# rpi_can.net
KiCad netlist of a schematic drawn in EAGLE
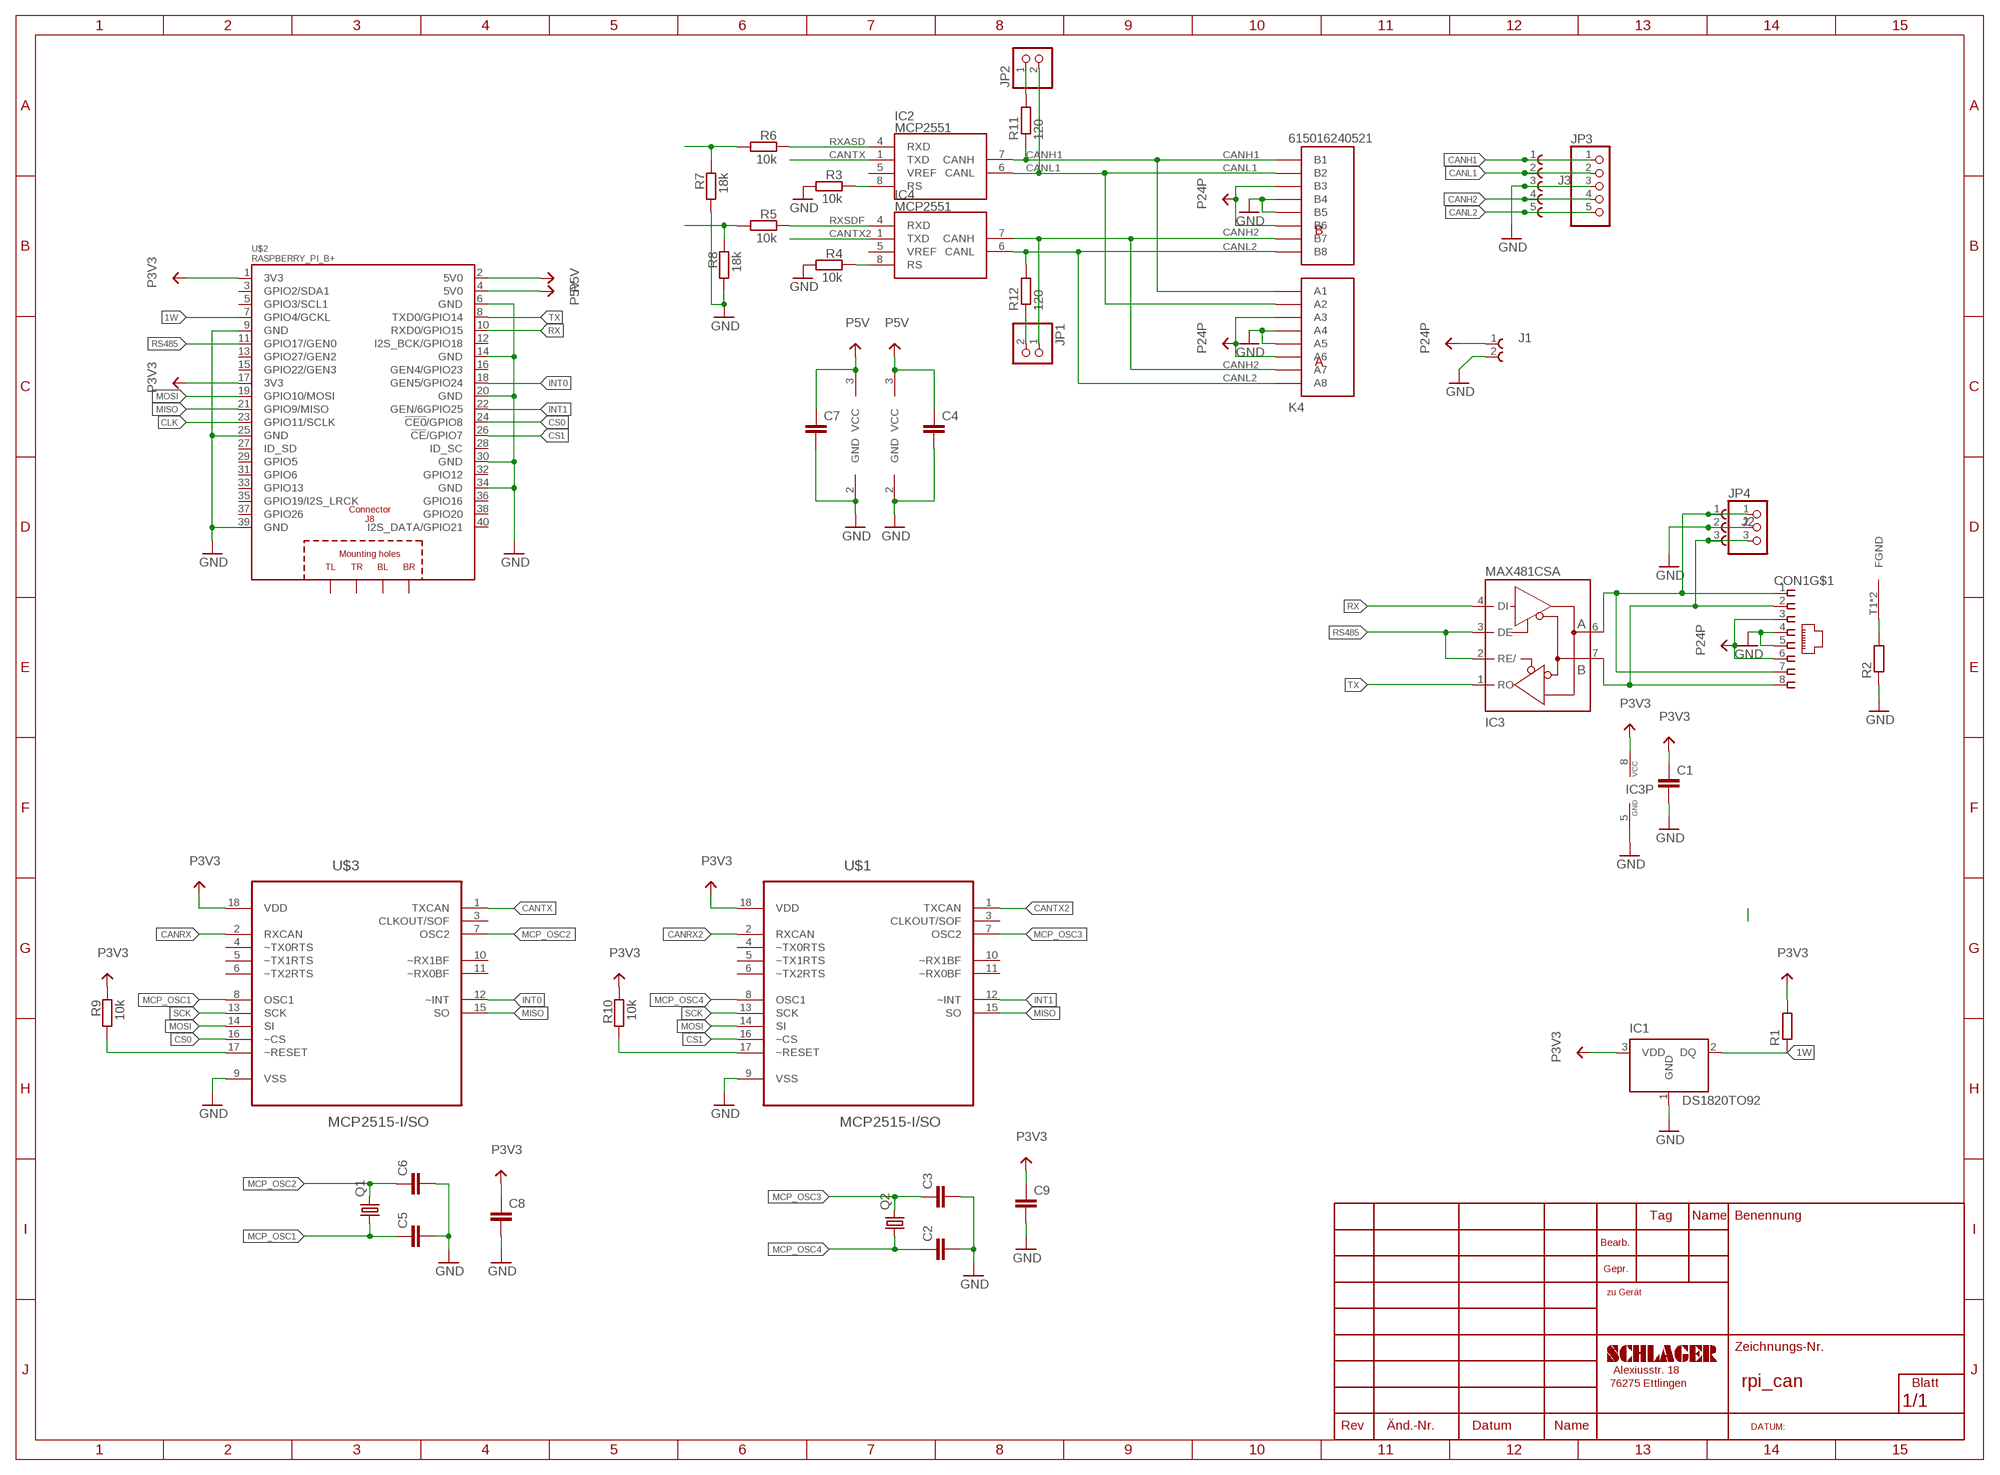
[diagram p0: schematic, sheet 1]

(export (version "E")
  (design (tool "Eeschema 10.0.6"))
  (components
    (comp (ref "C1")
      (value "C-EUC0805")
      (footprint "eagle-import:C0805")
      (libsource (lib "eagle-import") (part "C-EUC0805"))
    )
    (comp (ref "C2")
      (value "C-EUC0805")
      (footprint "eagle-import:C0805")
      (libsource (lib "eagle-import") (part "C-EUC0805"))
    )
    (comp (ref "C3")
      (value "C-EUC0805")
      (footprint "eagle-import:C0805")
      (libsource (lib "eagle-import") (part "C-EUC0805"))
    )
    (comp (ref "C4")
      (value "C-EUC0805")
      (footprint "eagle-import:C0805")
      (libsource (lib "eagle-import") (part "C-EUC0805"))
    )
    (comp (ref "C5")
      (value "C-EUC0805")
      (footprint "eagle-import:C0805")
      (libsource (lib "eagle-import") (part "C-EUC0805"))
    )
    (comp (ref "C6")
      (value "C-EUC0805")
      (footprint "eagle-import:C0805")
      (libsource (lib "eagle-import") (part "C-EUC0805"))
    )
    (comp (ref "C7")
      (value "C-EUC0805")
      (footprint "eagle-import:C0805")
      (libsource (lib "eagle-import") (part "C-EUC0805"))
    )
    (comp (ref "C8")
      (value "C-EUC0805")
      (footprint "eagle-import:C0805")
      (libsource (lib "eagle-import") (part "C-EUC0805"))
    )
    (comp (ref "C9")
      (value "C-EUC0805")
      (footprint "eagle-import:C0805")
      (libsource (lib "eagle-import") (part "C-EUC0805"))
    )
    (comp (ref "CON1")
      (value "MEBP_8-8G")
      (footprint "eagle-import:MEBP")
      (libsource (lib "eagle-import") (part "MEBP_8-8G"))
    )
    (comp (ref "IC1")
      (value "DS1820TO92")
      (footprint "eagle-import:TO-92")
      (libsource (lib "eagle-import") (part "DS1820TO92"))
    )
    (comp (ref "IC2")
      (value "MCP2551")
      (footprint "eagle-import:SO-8")
      (libsource (lib "eagle-import") (part "MCP2551"))
    )
    (comp (ref "IC3")
      (value "MAX481CSA")
      (footprint "eagle-import:SO08")
      (fields (field (name "MF") "MAXIM"))
      (libsource (lib "eagle-import") (part "MAX481CSA"))
    )
    (comp (ref "IC4")
      (value "MCP2551")
      (footprint "eagle-import:SO-8")
      (libsource (lib "eagle-import") (part "MCP2551"))
    )
    (comp (ref "J1")
      (value "691322310002")
      (footprint "eagle-import:691322310002")
      (libsource (lib "eagle-import") (part "691322310002"))
    )
    (comp (ref "J2")
      (value "691322310003")
      (footprint "eagle-import:691322310003")
      (libsource (lib "eagle-import") (part "691322310003"))
    )
    (comp (ref "J3")
      (value "691322310005")
      (footprint "eagle-import:691322310005")
      (libsource (lib "eagle-import") (part "691322310005"))
    )
    (comp (ref "JP1")
      (value "PINHD-1X2")
      (footprint "eagle-import:1X02")
      (libsource (lib "eagle-import") (part "PINHD-1X2"))
    )
    (comp (ref "JP2")
      (value "PINHD-1X2")
      (footprint "eagle-import:1X02")
      (libsource (lib "eagle-import") (part "PINHD-1X2"))
    )
    (comp (ref "JP3")
      (value "PINHD-1X5")
      (footprint "eagle-import:1X05")
      (libsource (lib "eagle-import") (part "PINHD-1X5"))
    )
    (comp (ref "JP4")
      (value "PINHD-1X3")
      (footprint "eagle-import:1X03")
      (libsource (lib "eagle-import") (part "PINHD-1X3"))
    )
    (comp (ref "K4")
      (value "615016240521")
      (footprint "eagle-import:615016240521")
      (libsource (lib "eagle-import") (part "615016240521"))
    )
    (comp (ref "Q1")
      (value "CRYSTALHC49S")
      (footprint "eagle-import:HC49_S")
      (libsource (lib "eagle-import") (part "CRYSTALHC49S"))
    )
    (comp (ref "Q2")
      (value "CRYSTALHC49S")
      (footprint "eagle-import:HC49_S")
      (libsource (lib "eagle-import") (part "CRYSTALHC49S"))
    )
    (comp (ref "R1")
      (value "R-EU_R0805")
      (footprint "eagle-import:R0805")
      (libsource (lib "eagle-import") (part "R-EU_R0805"))
    )
    (comp (ref "R2")
      (value "R-EU_R0805")
      (footprint "eagle-import:R0805")
      (libsource (lib "eagle-import") (part "R-EU_R0805"))
    )
    (comp (ref "R3")
      (value "10k")
      (footprint "eagle-import:R0805")
      (libsource (lib "eagle-import") (part "R-EU_R0805"))
    )
    (comp (ref "R4")
      (value "10k")
      (footprint "eagle-import:R0805")
      (libsource (lib "eagle-import") (part "R-EU_R0805"))
    )
    (comp (ref "R5")
      (value "10k")
      (footprint "eagle-import:R0805")
      (libsource (lib "eagle-import") (part "R-EU_R0805"))
    )
    (comp (ref "R6")
      (value "10k")
      (footprint "eagle-import:R0805")
      (libsource (lib "eagle-import") (part "R-EU_R0805"))
    )
    (comp (ref "R7")
      (value "18k")
      (footprint "eagle-import:R0805")
      (libsource (lib "eagle-import") (part "R-EU_R0805"))
    )
    (comp (ref "R8")
      (value "18k")
      (footprint "eagle-import:R0805")
      (libsource (lib "eagle-import") (part "R-EU_R0805"))
    )
    (comp (ref "R9")
      (value "10k")
      (footprint "eagle-import:R0805")
      (libsource (lib "eagle-import") (part "R-EU_R0805"))
    )
    (comp (ref "R10")
      (value "10k")
      (footprint "eagle-import:R0805")
      (libsource (lib "eagle-import") (part "R-EU_R0805"))
    )
    (comp (ref "R11")
      (value "120")
      (footprint "eagle-import:R0805")
      (libsource (lib "eagle-import") (part "R-EU_R0805"))
    )
    (comp (ref "R12")
      (value "120")
      (footprint "eagle-import:R0805")
      (libsource (lib "eagle-import") (part "R-EU_R0805"))
    )
    (comp (ref "U$1")
      (value "MCP2515-I/SO")
      (footprint "eagle-import:SOIC127P1034X264-18N")
      (libsource (lib "eagle-import") (part "MCP2515-I/SO"))
    )
    (comp (ref "U$2")
      (value "RASPBERRY_PI_B+")
      (footprint "eagle-import:RASPBERRY_PI_B+")
      (libsource (lib "eagle-import") (part "RASPBERRY_PI_B+"))
    )
    (comp (ref "U$3")
      (value "MCP2515-I/SO")
      (footprint "eagle-import:SOIC127P1034X264-18N")
      (libsource (lib "eagle-import") (part "MCP2515-I/SO"))
    )
  )
  (nets
    (net (code "1") (name "/RXASD") (class "Default")
      (node (ref "IC2") (pin "4") (pinfunction "RXD_4") (pintype "bidirectional"))
      (node (ref "R6") (pin "1") (pinfunction "1_1") (pintype "passive"))
    )
    (net (code "2") (name "/RXSDF") (class "Default")
      (node (ref "IC4") (pin "4") (pinfunction "RXD_4") (pintype "bidirectional"))
      (node (ref "R5") (pin "1") (pinfunction "1_1") (pintype "passive"))
    )
    (net (code "3") (name "1W") (class "Default")
      (node (ref "IC1") (pin "2") (pinfunction "DQ_2") (pintype "output"))
      (node (ref "R1") (pin "1") (pinfunction "1_1") (pintype "passive"))
      (node (ref "U$2") (pin "7") (pinfunction "GPIO4/GCKL_7") (pintype "bidirectional"))
    )
    (net (code "4") (name "CANH1") (class "Default")
      (node (ref "IC2") (pin "7") (pinfunction "CANH_7") (pintype "bidirectional"))
      (node (ref "J3") (pin "1") (pinfunction "1_1") (pintype "passive"))
      (node (ref "JP3") (pin "1") (pinfunction "1_1") (pintype "passive"))
      (node (ref "K4") (pin "A1") (pinfunction "A1_A1") (pintype "passive"))
      (node (ref "K4") (pin "B1") (pinfunction "B1_B1") (pintype "passive"))
      (node (ref "R11") (pin "1") (pinfunction "1_1") (pintype "passive"))
    )
    (net (code "5") (name "CANH2") (class "Default")
      (node (ref "IC4") (pin "7") (pinfunction "CANH_7") (pintype "bidirectional"))
      (node (ref "J3") (pin "4") (pinfunction "4_4") (pintype "passive"))
      (node (ref "JP1") (pin "1") (pinfunction "1_1") (pintype "passive"))
      (node (ref "JP3") (pin "4") (pinfunction "4_4") (pintype "passive"))
      (node (ref "K4") (pin "A7") (pinfunction "A7_A7") (pintype "passive"))
      (node (ref "K4") (pin "B7") (pinfunction "B7_B7") (pintype "passive"))
    )
    (net (code "6") (name "CANL1") (class "Default")
      (node (ref "IC2") (pin "6") (pinfunction "CANL_6") (pintype "bidirectional"))
      (node (ref "J3") (pin "2") (pinfunction "2_2") (pintype "passive"))
      (node (ref "JP2") (pin "2") (pinfunction "2_2") (pintype "passive"))
      (node (ref "JP3") (pin "2") (pinfunction "2_2") (pintype "passive"))
      (node (ref "K4") (pin "A2") (pinfunction "A2_A2") (pintype "passive"))
      (node (ref "K4") (pin "B2") (pinfunction "B2_B2") (pintype "passive"))
    )
    (net (code "7") (name "CANL2") (class "Default")
      (node (ref "IC4") (pin "6") (pinfunction "CANL_6") (pintype "bidirectional"))
      (node (ref "J3") (pin "5") (pinfunction "5_5") (pintype "passive"))
      (node (ref "JP3") (pin "5") (pinfunction "5_5") (pintype "passive"))
      (node (ref "K4") (pin "A8") (pinfunction "A8_A8") (pintype "passive"))
      (node (ref "K4") (pin "B8") (pinfunction "B8_B8") (pintype "passive"))
      (node (ref "R12") (pin "2") (pinfunction "2_2") (pintype "passive"))
    )
    (net (code "8") (name "CANRX") (class "Default")
      (node (ref "R6") (pin "2") (pinfunction "2_2") (pintype "passive"))
      (node (ref "R7") (pin "1") (pinfunction "1_1") (pintype "passive"))
      (node (ref "U$3") (pin "2") (pinfunction "RXCAN_2") (pintype "input"))
    )
    (net (code "9") (name "CANRX2") (class "Default")
      (node (ref "R5") (pin "2") (pinfunction "2_2") (pintype "passive"))
      (node (ref "R8") (pin "1") (pinfunction "1_1") (pintype "passive"))
      (node (ref "U$1") (pin "2") (pinfunction "RXCAN_2") (pintype "input"))
    )
    (net (code "10") (name "CANTX") (class "Default")
      (node (ref "IC2") (pin "1") (pinfunction "TXD_1") (pintype "bidirectional"))
      (node (ref "U$3") (pin "1") (pinfunction "TXCAN_1") (pintype "output"))
    )
    (net (code "11") (name "CANTX2") (class "Default")
      (node (ref "IC4") (pin "1") (pinfunction "TXD_1") (pintype "bidirectional"))
      (node (ref "U$1") (pin "1") (pinfunction "TXCAN_1") (pintype "output"))
    )
    (net (code "12") (name "CLK") (class "Default")
      (node (ref "U$2") (pin "23") (pinfunction "GPIO11/SCLK_23") (pintype "bidirectional"))
    )
    (net (code "13") (name "CS0") (class "Default")
      (node (ref "U$2") (pin "24") (pinfunction "~{CE0}/GPIO8_24") (pintype "bidirectional"))
      (node (ref "U$3") (pin "16") (pinfunction "~{CS}_16") (pintype "input"))
    )
    (net (code "14") (name "CS1") (class "Default")
      (node (ref "U$1") (pin "16") (pinfunction "~{CS}_16") (pintype "input"))
      (node (ref "U$2") (pin "26") (pinfunction "~{CE}/GPIO7_26") (pintype "bidirectional"))
    )
    (net (code "15") (name "GND") (class "Default")
      (node (ref "C1") (pin "2") (pinfunction "2_2") (pintype "passive"))
      (node (ref "C2") (pin "2") (pinfunction "2_2") (pintype "passive"))
      (node (ref "C3") (pin "2") (pinfunction "2_2") (pintype "passive"))
      (node (ref "C4") (pin "2") (pinfunction "2_2") (pintype "passive"))
      (node (ref "C5") (pin "2") (pinfunction "2_2") (pintype "passive"))
      (node (ref "C6") (pin "2") (pinfunction "2_2") (pintype "passive"))
      (node (ref "C7") (pin "2") (pinfunction "2_2") (pintype "passive"))
      (node (ref "C8") (pin "2") (pinfunction "2_2") (pintype "passive"))
      (node (ref "C9") (pin "2") (pinfunction "2_2") (pintype "passive"))
      (node (ref "CON1") (pin "4") (pinfunction "4_4") (pintype "passive"))
      (node (ref "CON1") (pin "5") (pinfunction "5_5") (pintype "passive"))
      (node (ref "IC1") (pin "1") (pinfunction "GND_1") (pintype "power_in"))
      (node (ref "IC2") (pin "2") (pinfunction "GND_2") (pintype "power_in"))
      (node (ref "IC3") (pin "5") (pinfunction "GND_5") (pintype "power_in"))
      (node (ref "IC4") (pin "2") (pinfunction "GND_2") (pintype "power_in"))
      (node (ref "J1") (pin "2") (pinfunction "2_2") (pintype "passive"))
      (node (ref "J2") (pin "2") (pinfunction "2_2") (pintype "passive"))
      (node (ref "J3") (pin "3") (pinfunction "3_3") (pintype "passive"))
      (node (ref "JP3") (pin "3") (pinfunction "3_3") (pintype "passive"))
      (node (ref "JP4") (pin "2") (pinfunction "2_2") (pintype "passive"))
      (node (ref "K4") (pin "A4") (pinfunction "A4_A4") (pintype "passive"))
      (node (ref "K4") (pin "A5") (pinfunction "A5_A5") (pintype "passive"))
      (node (ref "K4") (pin "B4") (pinfunction "B4_B4") (pintype "passive"))
      (node (ref "K4") (pin "B5") (pinfunction "B5_B5") (pintype "passive"))
      (node (ref "R2") (pin "1") (pinfunction "1_1") (pintype "passive"))
      (node (ref "R3") (pin "2") (pinfunction "2_2") (pintype "passive"))
      (node (ref "R4") (pin "2") (pinfunction "2_2") (pintype "passive"))
      (node (ref "R7") (pin "2") (pinfunction "2_2") (pintype "passive"))
      (node (ref "R8") (pin "2") (pinfunction "2_2") (pintype "passive"))
      (node (ref "U$1") (pin "9") (pinfunction "VSS_9") (pintype "power_in"))
      (node (ref "U$2") (pin "14") (pinfunction "GND_14") (pintype "power_in"))
      (node (ref "U$2") (pin "20") (pinfunction "GND_20") (pintype "power_in"))
      (node (ref "U$2") (pin "25") (pinfunction "GND_25") (pintype "power_in"))
      (node (ref "U$2") (pin "30") (pinfunction "GND_30") (pintype "power_in"))
      (node (ref "U$2") (pin "34") (pinfunction "GND_34") (pintype "power_in"))
      (node (ref "U$2") (pin "39") (pinfunction "GND_39") (pintype "power_in"))
      (node (ref "U$2") (pin "6") (pinfunction "GND_6") (pintype "power_in"))
      (node (ref "U$2") (pin "9") (pinfunction "GND_9") (pintype "power_in"))
      (node (ref "U$3") (pin "9") (pinfunction "VSS_9") (pintype "power_in"))
    )
    (net (code "16") (name "INT0") (class "Default")
      (node (ref "U$2") (pin "18") (pinfunction "GEN5/GPIO24_18") (pintype "bidirectional"))
      (node (ref "U$3") (pin "12") (pinfunction "~{INT}_12") (pintype "output"))
    )
    (net (code "17") (name "INT1") (class "Default")
      (node (ref "U$1") (pin "12") (pinfunction "~{INT}_12") (pintype "output"))
      (node (ref "U$2") (pin "22") (pinfunction "GEN/6GPIO25_22") (pintype "bidirectional"))
    )
    (net (code "18") (name "MCP_OSC1") (class "Default")
      (node (ref "C5") (pin "1") (pinfunction "1_1") (pintype "passive"))
      (node (ref "Q1") (pin "1") (pinfunction "1_1") (pintype "passive"))
      (node (ref "U$3") (pin "8") (pinfunction "OSC1_8") (pintype "input"))
    )
    (net (code "19") (name "MCP_OSC2") (class "Default")
      (node (ref "C6") (pin "1") (pinfunction "1_1") (pintype "passive"))
      (node (ref "Q1") (pin "2") (pinfunction "2_2") (pintype "passive"))
      (node (ref "U$3") (pin "7") (pinfunction "OSC2_7") (pintype "output"))
    )
    (net (code "20") (name "MCP_OSC3") (class "Default")
      (node (ref "C3") (pin "1") (pinfunction "1_1") (pintype "passive"))
      (node (ref "Q2") (pin "2") (pinfunction "2_2") (pintype "passive"))
      (node (ref "U$1") (pin "7") (pinfunction "OSC2_7") (pintype "output"))
    )
    (net (code "21") (name "MCP_OSC4") (class "Default")
      (node (ref "C2") (pin "1") (pinfunction "1_1") (pintype "passive"))
      (node (ref "Q2") (pin "1") (pinfunction "1_1") (pintype "passive"))
      (node (ref "U$1") (pin "8") (pinfunction "OSC1_8") (pintype "input"))
    )
    (net (code "22") (name "MISO") (class "Default")
      (node (ref "U$1") (pin "15") (pinfunction "SO_15") (pintype "output"))
      (node (ref "U$2") (pin "21") (pinfunction "GPIO9/MISO_21") (pintype "bidirectional"))
      (node (ref "U$3") (pin "15") (pinfunction "SO_15") (pintype "output"))
    )
    (net (code "23") (name "MOSI") (class "Default")
      (node (ref "U$1") (pin "14") (pinfunction "SI_14") (pintype "input"))
      (node (ref "U$2") (pin "19") (pinfunction "GPIO10/MOSI_19") (pintype "bidirectional"))
      (node (ref "U$3") (pin "14") (pinfunction "SI_14") (pintype "input"))
    )
    (net (code "24") (name "Net-(CON1B-FGND-PadT1)") (class "Default")
      (node (ref "CON1") (pin "T1") (pinfunction "FGND_T1") (pintype "power_in"))
      (node (ref "CON1") (pin "T2") (pinfunction "FGND_T2") (pintype "power_in"))
      (node (ref "R2") (pin "2") (pinfunction "2_2") (pintype "passive"))
    )
    (net (code "25") (name "Net-(IC2A-RS)") (class "Default")
      (node (ref "IC2") (pin "8") (pinfunction "RS_8") (pintype "bidirectional"))
      (node (ref "R3") (pin "1") (pinfunction "1_1") (pintype "passive"))
    )
    (net (code "26") (name "Net-(IC3A-A)") (class "Default")
      (node (ref "CON1") (pin "1") (pinfunction "1_1") (pintype "passive"))
      (node (ref "CON1") (pin "7") (pinfunction "7_7") (pintype "passive"))
      (node (ref "IC3") (pin "6") (pinfunction "A_6") (pintype "passive"))
      (node (ref "J2") (pin "1") (pinfunction "1_1") (pintype "passive"))
      (node (ref "JP4") (pin "1") (pinfunction "1_1") (pintype "passive"))
    )
    (net (code "27") (name "Net-(IC3A-B)") (class "Default")
      (node (ref "CON1") (pin "2") (pinfunction "2_2") (pintype "passive"))
      (node (ref "CON1") (pin "8") (pinfunction "8_8") (pintype "passive"))
      (node (ref "IC3") (pin "7") (pinfunction "B_7") (pintype "passive"))
      (node (ref "J2") (pin "3") (pinfunction "3_3") (pintype "passive"))
      (node (ref "JP4") (pin "3") (pinfunction "3_3") (pintype "passive"))
    )
    (net (code "28") (name "Net-(IC4A-RS)") (class "Default")
      (node (ref "IC4") (pin "8") (pinfunction "RS_8") (pintype "bidirectional"))
      (node (ref "R4") (pin "1") (pinfunction "1_1") (pintype "passive"))
    )
    (net (code "29") (name "Net-(JP1-Pad2)") (class "Default")
      (node (ref "JP1") (pin "2") (pinfunction "2_2") (pintype "passive"))
      (node (ref "R12") (pin "1") (pinfunction "1_1") (pintype "passive"))
    )
    (net (code "30") (name "Net-(JP2-Pad1)") (class "Default")
      (node (ref "JP2") (pin "1") (pinfunction "1_1") (pintype "passive"))
      (node (ref "R11") (pin "2") (pinfunction "2_2") (pintype "passive"))
    )
    (net (code "31") (name "Net-(U$1-~{RESET})") (class "Default")
      (node (ref "R10") (pin "2") (pinfunction "2_2") (pintype "passive"))
      (node (ref "U$1") (pin "17") (pinfunction "~{RESET}_17") (pintype "input"))
    )
    (net (code "32") (name "Net-(U$3-~{RESET})") (class "Default")
      (node (ref "R9") (pin "2") (pinfunction "2_2") (pintype "passive"))
      (node (ref "U$3") (pin "17") (pinfunction "~{RESET}_17") (pintype "input"))
    )
    (net (code "33") (name "P3V3") (class "Default")
      (node (ref "C1") (pin "1") (pinfunction "1_1") (pintype "passive"))
      (node (ref "C8") (pin "1") (pinfunction "1_1") (pintype "passive"))
      (node (ref "C9") (pin "1") (pinfunction "1_1") (pintype "passive"))
      (node (ref "IC1") (pin "3") (pinfunction "VDD_3") (pintype "input"))
      (node (ref "IC3") (pin "8") (pinfunction "VCC_8") (pintype "power_in"))
      (node (ref "R1") (pin "2") (pinfunction "2_2") (pintype "passive"))
      (node (ref "R10") (pin "1") (pinfunction "1_1") (pintype "passive"))
      (node (ref "R9") (pin "1") (pinfunction "1_1") (pintype "passive"))
      (node (ref "U$1") (pin "18") (pinfunction "VDD_18") (pintype "power_in"))
      (node (ref "U$2") (pin "1") (pinfunction "3V3_1") (pintype "power_in"))
      (node (ref "U$2") (pin "17") (pinfunction "3V3_17") (pintype "power_in"))
      (node (ref "U$3") (pin "18") (pinfunction "VDD_18") (pintype "power_in"))
    )
    (net (code "34") (name "P5V") (class "Default")
      (node (ref "C4") (pin "1") (pinfunction "1_1") (pintype "passive"))
      (node (ref "C7") (pin "1") (pinfunction "1_1") (pintype "passive"))
      (node (ref "IC2") (pin "3") (pinfunction "VCC_3") (pintype "power_in"))
      (node (ref "IC4") (pin "3") (pinfunction "VCC_3") (pintype "power_in"))
      (node (ref "U$2") (pin "2") (pinfunction "5V0_2") (pintype "power_in"))
      (node (ref "U$2") (pin "4") (pinfunction "5V0_4") (pintype "power_in"))
    )
    (net (code "35") (name "P24P") (class "Default")
      (node (ref "CON1") (pin "3") (pinfunction "3_3") (pintype "passive"))
      (node (ref "CON1") (pin "6") (pinfunction "6_6") (pintype "passive"))
      (node (ref "J1") (pin "1") (pinfunction "1_1") (pintype "passive"))
      (node (ref "K4") (pin "A3") (pinfunction "A3_A3") (pintype "passive"))
      (node (ref "K4") (pin "A6") (pinfunction "A6_A6") (pintype "passive"))
      (node (ref "K4") (pin "B3") (pinfunction "B3_B3") (pintype "passive"))
      (node (ref "K4") (pin "B6") (pinfunction "B6_B6") (pintype "passive"))
    )
    (net (code "36") (name "RS485") (class "Default")
      (node (ref "IC3") (pin "2") (pinfunction "RE/_2") (pintype "input"))
      (node (ref "IC3") (pin "3") (pinfunction "DE_3") (pintype "input"))
      (node (ref "U$2") (pin "11") (pinfunction "GPIO17/GEN0_11") (pintype "bidirectional"))
    )
    (net (code "37") (name "RX") (class "Default")
      (node (ref "IC3") (pin "4") (pinfunction "DI_4") (pintype "input"))
      (node (ref "U$2") (pin "10") (pinfunction "RXD0/GPIO15_10") (pintype "bidirectional"))
    )
    (net (code "38") (name "SCK") (class "Default")
      (node (ref "U$1") (pin "13") (pinfunction "SCK_13") (pintype "input"))
      (node (ref "U$3") (pin "13") (pinfunction "SCK_13") (pintype "input"))
    )
    (net (code "39") (name "TX") (class "Default")
      (node (ref "IC3") (pin "1") (pinfunction "RO_1") (pintype "output"))
      (node (ref "U$2") (pin "8") (pinfunction "TXD0/GPIO14_8") (pintype "bidirectional"))
    )
    (net (code "40") (name "unconnected-(IC2A-VREF-Pad5)") (class "Default")
      (node (ref "IC2") (pin "5") (pinfunction "VREF_5") (pintype "bidirectional"))
    )
    (net (code "41") (name "unconnected-(IC4A-VREF-Pad5)") (class "Default")
      (node (ref "IC4") (pin "5") (pinfunction "VREF_5") (pintype "bidirectional"))
    )
    (net (code "42") (name "unconnected-(U$1-CLKOUT{slash}SOF-Pad3)") (class "Default")
      (node (ref "U$1") (pin "3") (pinfunction "CLKOUT/SOF_3") (pintype "output"))
    )
    (net (code "43") (name "unconnected-(U$1-~{RX0BF}-Pad11)") (class "Default")
      (node (ref "U$1") (pin "11") (pinfunction "~{RX0BF}_11") (pintype "output"))
    )
    (net (code "44") (name "unconnected-(U$1-~{RX1BF}-Pad10)") (class "Default")
      (node (ref "U$1") (pin "10") (pinfunction "~{RX1BF}_10") (pintype "output"))
    )
    (net (code "45") (name "unconnected-(U$1-~{TX0RTS}-Pad4)") (class "Default")
      (node (ref "U$1") (pin "4") (pinfunction "~{TX0RTS}_4") (pintype "input"))
    )
    (net (code "46") (name "unconnected-(U$1-~{TX1RTS}-Pad5)") (class "Default")
      (node (ref "U$1") (pin "5") (pinfunction "~{TX1RTS}_5") (pintype "input"))
    )
    (net (code "47") (name "unconnected-(U$1-~{TX2RTS}-Pad6)") (class "Default")
      (node (ref "U$1") (pin "6") (pinfunction "~{TX2RTS}_6") (pintype "input"))
    )
    (net (code "48") (name "unconnected-(U$2-BL-PadPE_BL)") (class "Default")
      (node (ref "U$2") (pin "PE_BL") (pinfunction "BL_PE_BL") (pintype "bidirectional"))
    )
    (net (code "49") (name "unconnected-(U$2-BR-PadPE_BR)") (class "Default")
      (node (ref "U$2") (pin "PE_BR") (pinfunction "BR_PE_BR") (pintype "bidirectional"))
    )
    (net (code "50") (name "unconnected-(U$2-GEN4{slash}GPIO23-Pad16)") (class "Default")
      (node (ref "U$2") (pin "16") (pinfunction "GEN4/GPIO23_16") (pintype "bidirectional"))
    )
    (net (code "51") (name "unconnected-(U$2-GPIO2{slash}SDA1-Pad3)") (class "Default")
      (node (ref "U$2") (pin "3") (pinfunction "GPIO2/SDA1_3") (pintype "bidirectional"))
    )
    (net (code "52") (name "unconnected-(U$2-GPIO3{slash}SCL1-Pad5)") (class "Default")
      (node (ref "U$2") (pin "5") (pinfunction "GPIO3/SCL1_5") (pintype "bidirectional"))
    )
    (net (code "53") (name "unconnected-(U$2-GPIO5-Pad29)") (class "Default")
      (node (ref "U$2") (pin "29") (pinfunction "GPIO5_29") (pintype "bidirectional"))
    )
    (net (code "54") (name "unconnected-(U$2-GPIO6-Pad31)") (class "Default")
      (node (ref "U$2") (pin "31") (pinfunction "GPIO6_31") (pintype "bidirectional"))
    )
    (net (code "55") (name "unconnected-(U$2-GPIO12-Pad32)") (class "Default")
      (node (ref "U$2") (pin "32") (pinfunction "GPIO12_32") (pintype "bidirectional"))
    )
    (net (code "56") (name "unconnected-(U$2-GPIO13-Pad33)") (class "Default")
      (node (ref "U$2") (pin "33") (pinfunction "GPIO13_33") (pintype "bidirectional"))
    )
    (net (code "57") (name "unconnected-(U$2-GPIO16-Pad36)") (class "Default")
      (node (ref "U$2") (pin "36") (pinfunction "GPIO16_36") (pintype "bidirectional"))
    )
    (net (code "58") (name "unconnected-(U$2-GPIO19{slash}I2S_LRCK-Pad35)") (class "Default")
      (node (ref "U$2") (pin "35") (pinfunction "GPIO19/I2S_LRCK_35") (pintype "bidirectional"))
    )
    (net (code "59") (name "unconnected-(U$2-GPIO20-Pad38)") (class "Default")
      (node (ref "U$2") (pin "38") (pinfunction "GPIO20_38") (pintype "bidirectional"))
    )
    (net (code "60") (name "unconnected-(U$2-GPIO22{slash}GEN3-Pad15)") (class "Default")
      (node (ref "U$2") (pin "15") (pinfunction "GPIO22/GEN3_15") (pintype "bidirectional"))
    )
    (net (code "61") (name "unconnected-(U$2-GPIO26-Pad37)") (class "Default")
      (node (ref "U$2") (pin "37") (pinfunction "GPIO26_37") (pintype "bidirectional"))
    )
    (net (code "62") (name "unconnected-(U$2-GPIO27{slash}GEN2-Pad13)") (class "Default")
      (node (ref "U$2") (pin "13") (pinfunction "GPIO27/GEN2_13") (pintype "bidirectional"))
    )
    (net (code "63") (name "unconnected-(U$2-I2S_BCK{slash}GPIO18-Pad12)") (class "Default")
      (node (ref "U$2") (pin "12") (pinfunction "I2S_BCK/GPIO18_12") (pintype "bidirectional"))
    )
    (net (code "64") (name "unconnected-(U$2-I2S_DATA{slash}GPIO21-Pad40)") (class "Default")
      (node (ref "U$2") (pin "40") (pinfunction "I2S_DATA/GPIO21_40") (pintype "bidirectional"))
    )
    (net (code "65") (name "unconnected-(U$2-ID_SC-Pad28)") (class "Default")
      (node (ref "U$2") (pin "28") (pinfunction "ID_SC_28") (pintype "bidirectional"))
    )
    (net (code "66") (name "unconnected-(U$2-ID_SD-Pad27)") (class "Default")
      (node (ref "U$2") (pin "27") (pinfunction "ID_SD_27") (pintype "bidirectional"))
    )
    (net (code "67") (name "unconnected-(U$2-TL-PadPE_TL)") (class "Default")
      (node (ref "U$2") (pin "PE_TL") (pinfunction "TL_PE_TL") (pintype "bidirectional"))
    )
    (net (code "68") (name "unconnected-(U$2-TR-PadPE_TR)") (class "Default")
      (node (ref "U$2") (pin "PE_TR") (pinfunction "TR_PE_TR") (pintype "bidirectional"))
    )
    (net (code "69") (name "unconnected-(U$3-CLKOUT{slash}SOF-Pad3)") (class "Default")
      (node (ref "U$3") (pin "3") (pinfunction "CLKOUT/SOF_3") (pintype "output"))
    )
    (net (code "70") (name "unconnected-(U$3-~{RX0BF}-Pad11)") (class "Default")
      (node (ref "U$3") (pin "11") (pinfunction "~{RX0BF}_11") (pintype "output"))
    )
    (net (code "71") (name "unconnected-(U$3-~{RX1BF}-Pad10)") (class "Default")
      (node (ref "U$3") (pin "10") (pinfunction "~{RX1BF}_10") (pintype "output"))
    )
    (net (code "72") (name "unconnected-(U$3-~{TX0RTS}-Pad4)") (class "Default")
      (node (ref "U$3") (pin "4") (pinfunction "~{TX0RTS}_4") (pintype "input"))
    )
    (net (code "73") (name "unconnected-(U$3-~{TX1RTS}-Pad5)") (class "Default")
      (node (ref "U$3") (pin "5") (pinfunction "~{TX1RTS}_5") (pintype "input"))
    )
    (net (code "74") (name "unconnected-(U$3-~{TX2RTS}-Pad6)") (class "Default")
      (node (ref "U$3") (pin "6") (pinfunction "~{TX2RTS}_6") (pintype "input"))
    )
  )
)
